# USB.net
KiCad netlist of a schematic drawn in Altium Designer
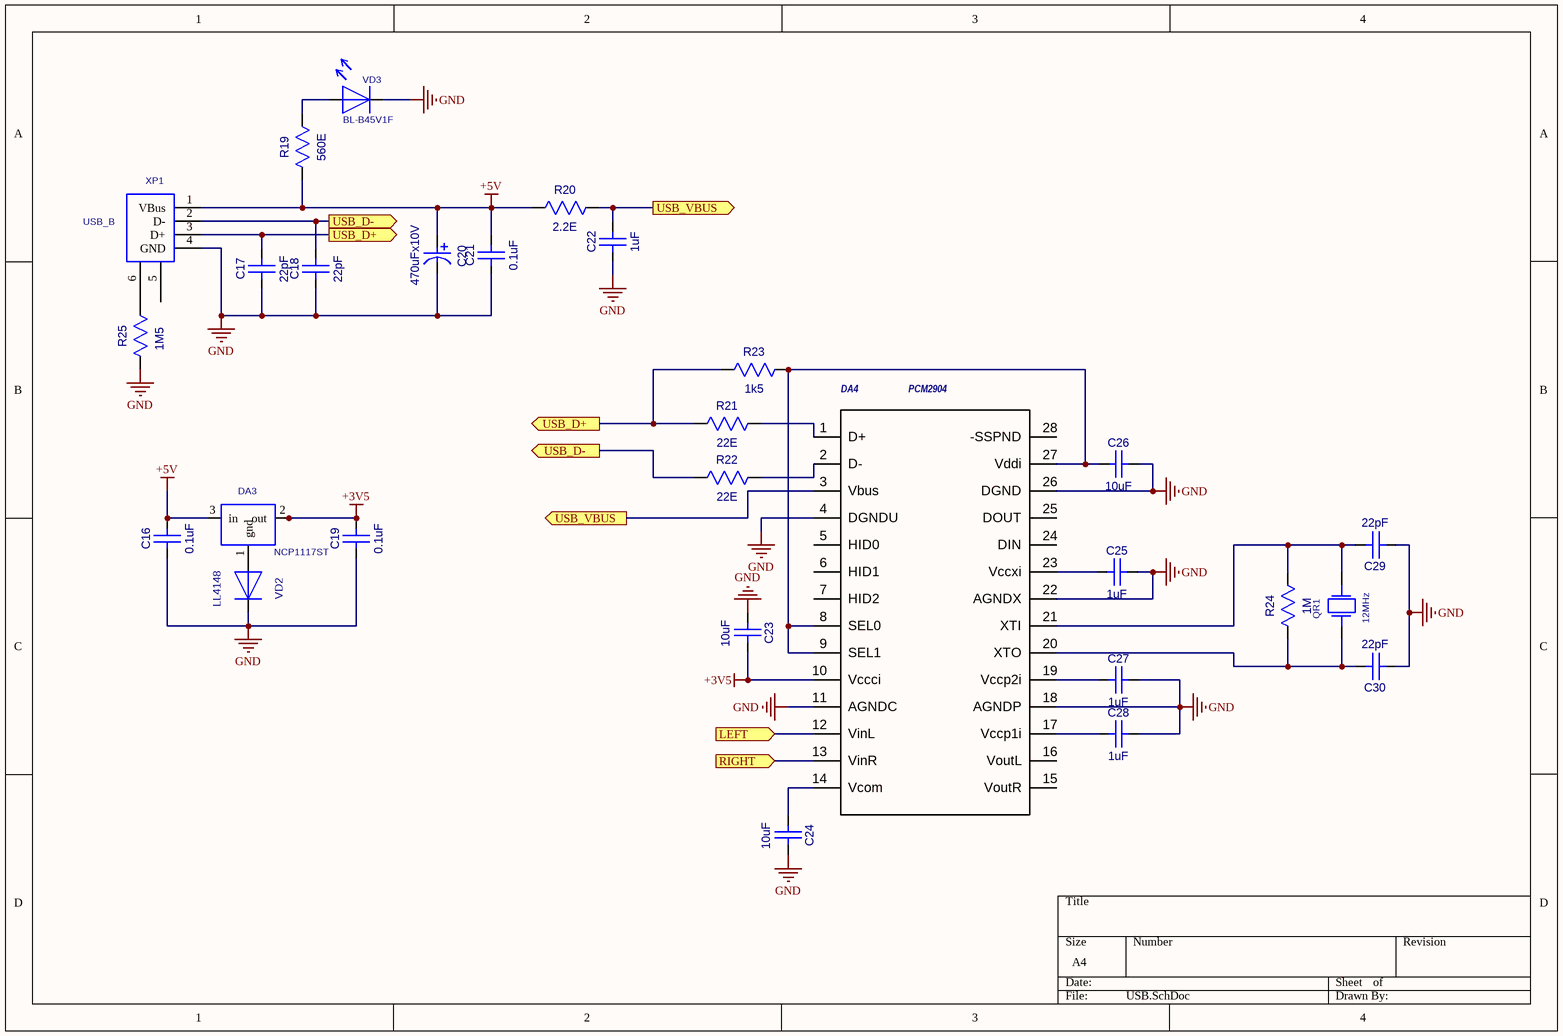
[diagram p0: USB.SchDoc]

(export (version "E")
  (design (tool "Eeschema 10.0.6"))
  (components
    (comp (ref "C16")
      (value "0.1uF")
      (footprint "CC0603-3M")
      (description "CC0603")
      (libsource (lib "Schetchik") (part "CC0603"))
    )
    (comp (ref "C17")
      (value "22pF")
      (footprint "CC0603-3M")
      (description "CC0603")
      (libsource (lib "gprs_modem") (part "CC0603"))
    )
    (comp (ref "C18")
      (value "22pF")
      (footprint "CC0603-3M")
      (description "CC0603")
      (libsource (lib "gprs_modem") (part "CC0603"))
    )
    (comp (ref "C19")
      (value "0.1uF")
      (footprint "CC0603-3M")
      (description "CC0603")
      (libsource (lib "Schetchik") (part "CC0603"))
    )
    (comp (ref "C20")
      (value "470uFx10V")
      (footprint "CC8X3.5")
      (description "CAP0.35")
      (libsource (lib "gprs_modem") (part "CAP0.35"))
    )
    (comp (ref "C21")
      (value "0.1uF")
      (footprint "CC0603-3M")
      (description "CC0603")
      (libsource (lib "gprs_modem") (part "CC0603"))
    )
    (comp (ref "C22")
      (value "1uF")
      (footprint "CC0603-3M")
      (description "CC0603")
      (libsource (lib "gprs_modem") (part "CC0603"))
    )
    (comp (ref "C23")
      (value "10uF")
      (footprint "CC0805-MIDI-2M1")
      (description "CC0805")
      (libsource (lib "gprs_modem") (part "CC0805"))
    )
    (comp (ref "C24")
      (value "10uF")
      (footprint "CC0805-MIDI-2M1")
      (description "CC0805")
      (libsource (lib "gprs_modem") (part "CC0805"))
    )
    (comp (ref "C25")
      (value "1uF")
      (footprint "CC0603-3M")
      (description "CC0603")
      (libsource (lib "") (part "CC0603_1"))
    )
    (comp (ref "C26")
      (value "10uF")
      (footprint "CC0805-MIDI-2M1")
      (description "CC0805")
      (libsource (lib "gprs_modem") (part "CC0805"))
    )
    (comp (ref "C27")
      (value "1uF")
      (footprint "CC0603-3M")
      (description "CC0603")
      (libsource (lib "gprs_modem") (part "CC0603"))
    )
    (comp (ref "C28")
      (value "1uF")
      (footprint "CC0603-3M")
      (description "CC0603")
      (libsource (lib "gprs_modem") (part "CC0603"))
    )
    (comp (ref "C29")
      (value "22pF")
      (footprint "CC0603-3M")
      (description "CC0603")
      (libsource (lib "gprs_modem") (part "CC0603"))
    )
    (comp (ref "C30")
      (value "22pF")
      (footprint "CC0603-3M")
      (description "CC0603")
      (libsource (lib "gprs_modem") (part "CC0603"))
    )
    (comp (ref "DA3")
      (value "NCP1117ST")
      (footprint "SOT-223")
      (libsource (lib "Schetchik") (part "NCP1117ST"))
    )
    (comp (ref "DA4") (value "PCM2904") (footprint "TSSOP28") (libsource (lib "*") (part "PCM2904")))
    (comp (ref "QR1")
      (value "12MHz")
      (footprint "HC-49")
      (description "LP-3.5")
      (libsource (lib "gprs_modem_2") (part "LP-3.5"))
    )
    (comp (ref "R19")
      (value "560E")
      (footprint "RC0603-3M")
      (description "RC0603")
      (libsource (lib "gprs_modem") (part "RC0603"))
    )
    (comp (ref "R20")
      (value "2.2E")
      (footprint "RC0805_IPC_NOM")
      (description "RC0805")
      (libsource (lib "gprs_modem") (part "RC0805"))
    )
    (comp (ref "R21")
      (value "22E")
      (footprint "RC0603-3M")
      (description "RC0603")
      (libsource (lib "gprs_modem") (part "RC0603"))
    )
    (comp (ref "R22")
      (value "22E")
      (footprint "RC0603-3M")
      (description "RC0603")
      (libsource (lib "gprs_modem") (part "RC0603"))
    )
    (comp (ref "R23")
      (value "1k5")
      (footprint "RC0603-3M")
      (description "RC0603")
      (libsource (lib "gprs_modem") (part "RC0603"))
    )
    (comp (ref "R24")
      (value "1M")
      (footprint "RC0603-3M")
      (description "RC0603")
      (libsource (lib "gprs_modem") (part "RC0603"))
    )
    (comp (ref "R25")
      (value "1M5")
      (footprint "RC1206-2M")
      (description "RC1206")
      (libsource (lib "gprs_modem") (part "RC1206"))
    )
    (comp (ref "VD2") (value "LL4148") (footprint "SOD-80") (libsource (lib "gprs_modem") (part "LL4148")))
    (comp (ref "VD3")
      (value "BL-B45V1F")
      (footprint "LED3")
      (description "LED_3")
      (libsource (lib "gprs_modem") (part "LED_3"))
    )
    (comp (ref "XP1") (value "USB_B") (footprint "USB-B") (libsource (lib "gprs_modem") (part "USB_B")))
  )
  (nets
    (net (code "1") (name "+3V5") (class "Default")
      (node (ref "C19") (pin "2") (pinfunction "B_2") (pintype "passive"))
      (node (ref "C23") (pin "2") (pinfunction "B_2") (pintype "passive"))
      (node (ref "DA3") (pin "2") (pinfunction "out_2") (pintype "passive"))
      (node (ref "DA3") (pin "4") (pintype "passive"))
      (node (ref "DA4") (pin "10") (pinfunction "Vccci_10") (pintype "passive"))
    )
    (net (code "2") (name "+5V") (class "Default")
      (node (ref "C16") (pin "2") (pinfunction "B_2") (pintype "passive"))
      (node (ref "C20") (pin "1") (pintype "passive"))
      (node (ref "C21") (pin "2") (pinfunction "B_2") (pintype "passive"))
      (node (ref "DA3") (pin "3") (pinfunction "in_3") (pintype "passive"))
      (node (ref "R19") (pin "1") (pinfunction "A_1") (pintype "passive"))
      (node (ref "R20") (pin "1") (pinfunction "A_1") (pintype "passive"))
      (node (ref "XP1") (pin "1") (pinfunction "VBus_1") (pintype "passive"))
    )
    (net (code "3") (name "/LEFT") (class "Default")
      (node (ref "DA4") (pin "12") (pinfunction "VinL_12") (pintype "passive"))
    )
    (net (code "4") (name "/RIGHT") (class "Default")
      (node (ref "DA4") (pin "13") (pinfunction "VinR_13") (pintype "passive"))
    )
    (net (code "5") (name "/USB_D+") (class "Default")
      (node (ref "C17") (pin "2") (pinfunction "B_2") (pintype "passive"))
      (node (ref "R21") (pin "1") (pinfunction "A_1") (pintype "passive"))
      (node (ref "R23") (pin "1") (pinfunction "A_1") (pintype "passive"))
      (node (ref "XP1") (pin "3") (pinfunction "D+_3") (pintype "passive"))
    )
    (net (code "6") (name "/USB_D-") (class "Default")
      (node (ref "C18") (pin "2") (pinfunction "B_2") (pintype "passive"))
      (node (ref "R22") (pin "1") (pinfunction "A_1") (pintype "passive"))
      (node (ref "XP1") (pin "2") (pinfunction "D-_2") (pintype "passive"))
    )
    (net (code "7") (name "/USB_VBUS") (class "Default")
      (node (ref "C22") (pin "2") (pinfunction "B_2") (pintype "passive"))
      (node (ref "DA4") (pin "3") (pinfunction "Vbus_3") (pintype "passive"))
      (node (ref "R20") (pin "2") (pinfunction "B_2") (pintype "passive"))
    )
    (net (code "8") (name "GND") (class "Default")
      (node (ref "C16") (pin "1") (pinfunction "A_1") (pintype "passive"))
      (node (ref "C17") (pin "1") (pinfunction "A_1") (pintype "passive"))
      (node (ref "C18") (pin "1") (pinfunction "A_1") (pintype "passive"))
      (node (ref "C19") (pin "1") (pinfunction "A_1") (pintype "passive"))
      (node (ref "C20") (pin "2") (pintype "passive"))
      (node (ref "C21") (pin "1") (pinfunction "A_1") (pintype "passive"))
      (node (ref "C22") (pin "1") (pinfunction "A_1") (pintype "passive"))
      (node (ref "C23") (pin "1") (pinfunction "A_1") (pintype "passive"))
      (node (ref "C24") (pin "2") (pinfunction "B_2") (pintype "passive"))
      (node (ref "C25") (pin "2") (pinfunction "B_2") (pintype "passive"))
      (node (ref "C26") (pin "2") (pinfunction "B_2") (pintype "passive"))
      (node (ref "C27") (pin "2") (pinfunction "B_2") (pintype "passive"))
      (node (ref "C28") (pin "2") (pinfunction "B_2") (pintype "passive"))
      (node (ref "C29") (pin "1") (pinfunction "A_1") (pintype "passive"))
      (node (ref "C30") (pin "1") (pinfunction "A_1") (pintype "passive"))
      (node (ref "DA4") (pin "11") (pinfunction "AGNDC_11") (pintype "passive"))
      (node (ref "DA4") (pin "18") (pinfunction "AGNDP_18") (pintype "passive"))
      (node (ref "DA4") (pin "22") (pinfunction "AGNDX_22") (pintype "passive"))
      (node (ref "DA4") (pin "26") (pinfunction "DGND_26") (pintype "passive"))
      (node (ref "DA4") (pin "4") (pinfunction "DGNDU_4") (pintype "passive"))
      (node (ref "R25") (pin "1") (pinfunction "A_1") (pintype "passive"))
      (node (ref "VD2") (pin "2") (pinfunction "+_2") (pintype "passive"))
      (node (ref "VD3") (pin "1") (pintype "passive"))
      (node (ref "XP1") (pin "4") (pinfunction "GND_4") (pintype "passive"))
    )
    (net (code "9") (name "Net-(C24-A)") (class "Default")
      (node (ref "C24") (pin "1") (pinfunction "A_1") (pintype "passive"))
      (node (ref "DA4") (pin "14") (pinfunction "Vcom_14") (pintype "passive"))
    )
    (net (code "10") (name "Net-(C25-A)") (class "Default")
      (node (ref "C25") (pin "1") (pinfunction "A_1") (pintype "passive"))
      (node (ref "DA4") (pin "23") (pinfunction "Vccxi_23") (pintype "passive"))
    )
    (net (code "11") (name "Net-(C26-A)") (class "Default")
      (node (ref "C26") (pin "1") (pinfunction "A_1") (pintype "passive"))
      (node (ref "DA4") (pin "27") (pinfunction "Vddi_27") (pintype "passive"))
      (node (ref "DA4") (pin "8") (pinfunction "SEL0_8") (pintype "passive"))
      (node (ref "DA4") (pin "9") (pinfunction "SEL1_9") (pintype "passive"))
      (node (ref "R23") (pin "2") (pinfunction "B_2") (pintype "passive"))
    )
    (net (code "12") (name "Net-(C27-A)") (class "Default")
      (node (ref "C27") (pin "1") (pinfunction "A_1") (pintype "passive"))
      (node (ref "DA4") (pin "19") (pinfunction "Vccp2i_19") (pintype "passive"))
    )
    (net (code "13") (name "Net-(C28-A)") (class "Default")
      (node (ref "C28") (pin "1") (pinfunction "A_1") (pintype "passive"))
      (node (ref "DA4") (pin "17") (pinfunction "Vccp1i_17") (pintype "passive"))
    )
    (net (code "14") (name "Net-(C29-B)") (class "Default")
      (node (ref "C29") (pin "2") (pinfunction "B_2") (pintype "passive"))
      (node (ref "DA4") (pin "21") (pinfunction "XTI_21") (pintype "passive"))
      (node (ref "QR1") (pin "2") (pintype "passive"))
      (node (ref "R24") (pin "2") (pinfunction "B_2") (pintype "passive"))
    )
    (net (code "15") (name "Net-(C30-B)") (class "Default")
      (node (ref "C30") (pin "2") (pinfunction "B_2") (pintype "passive"))
      (node (ref "DA4") (pin "20") (pinfunction "XTO_20") (pintype "passive"))
      (node (ref "QR1") (pin "1") (pintype "passive"))
      (node (ref "R24") (pin "1") (pinfunction "A_1") (pintype "passive"))
    )
    (net (code "16") (name "Net-(DA3-gnd)") (class "Default")
      (node (ref "DA3") (pin "1") (pinfunction "gnd_1") (pintype "passive"))
      (node (ref "VD2") (pin "1") (pinfunction "-_1") (pintype "passive"))
    )
    (net (code "17") (name "Net-(DA4-D+)") (class "Default")
      (node (ref "DA4") (pin "1") (pinfunction "D+_1") (pintype "passive"))
      (node (ref "R21") (pin "2") (pinfunction "B_2") (pintype "passive"))
    )
    (net (code "18") (name "Net-(DA4-D-)") (class "Default")
      (node (ref "DA4") (pin "2") (pinfunction "D-_2") (pintype "passive"))
      (node (ref "R22") (pin "2") (pinfunction "B_2") (pintype "passive"))
    )
    (net (code "19") (name "Net-(R19-B)") (class "Default")
      (node (ref "R19") (pin "2") (pinfunction "B_2") (pintype "passive"))
      (node (ref "VD3") (pin "2") (pintype "passive"))
    )
    (net (code "20") (name "Net-(R25-B)") (class "Default")
      (node (ref "R25") (pin "2") (pinfunction "B_2") (pintype "passive"))
      (node (ref "XP1") (pin "6") (pintype "passive"))
    )
    (net (code "21") (name "unconnected-(DA4--SSPND-Pad28)") (class "Default")
      (node (ref "DA4") (pin "28") (pinfunction "-SSPND_28") (pintype "passive"))
    )
    (net (code "22") (name "unconnected-(DA4-DIN-Pad24)") (class "Default")
      (node (ref "DA4") (pin "24") (pinfunction "DIN_24") (pintype "passive"))
    )
    (net (code "23") (name "unconnected-(DA4-DOUT-Pad25)") (class "Default")
      (node (ref "DA4") (pin "25") (pinfunction "DOUT_25") (pintype "passive"))
    )
    (net (code "24") (name "unconnected-(DA4-HID0-Pad5)") (class "Default")
      (node (ref "DA4") (pin "5") (pinfunction "HID0_5") (pintype "passive"))
    )
    (net (code "25") (name "unconnected-(DA4-HID1-Pad6)") (class "Default")
      (node (ref "DA4") (pin "6") (pinfunction "HID1_6") (pintype "passive"))
    )
    (net (code "26") (name "unconnected-(DA4-HID2-Pad7)") (class "Default")
      (node (ref "DA4") (pin "7") (pinfunction "HID2_7") (pintype "passive"))
    )
    (net (code "27") (name "unconnected-(DA4-VoutL-Pad16)") (class "Default")
      (node (ref "DA4") (pin "16") (pinfunction "VoutL_16") (pintype "passive"))
    )
    (net (code "28") (name "unconnected-(DA4-VoutR-Pad15)") (class "Default")
      (node (ref "DA4") (pin "15") (pinfunction "VoutR_15") (pintype "passive"))
    )
    (net (code "29") (name "unconnected-(XP1-Pad5)") (class "Default")
      (node (ref "XP1") (pin "5") (pintype "passive"))
    )
  )
)
